# board.net
KiCad netlist of a schematic drawn in EAGLE
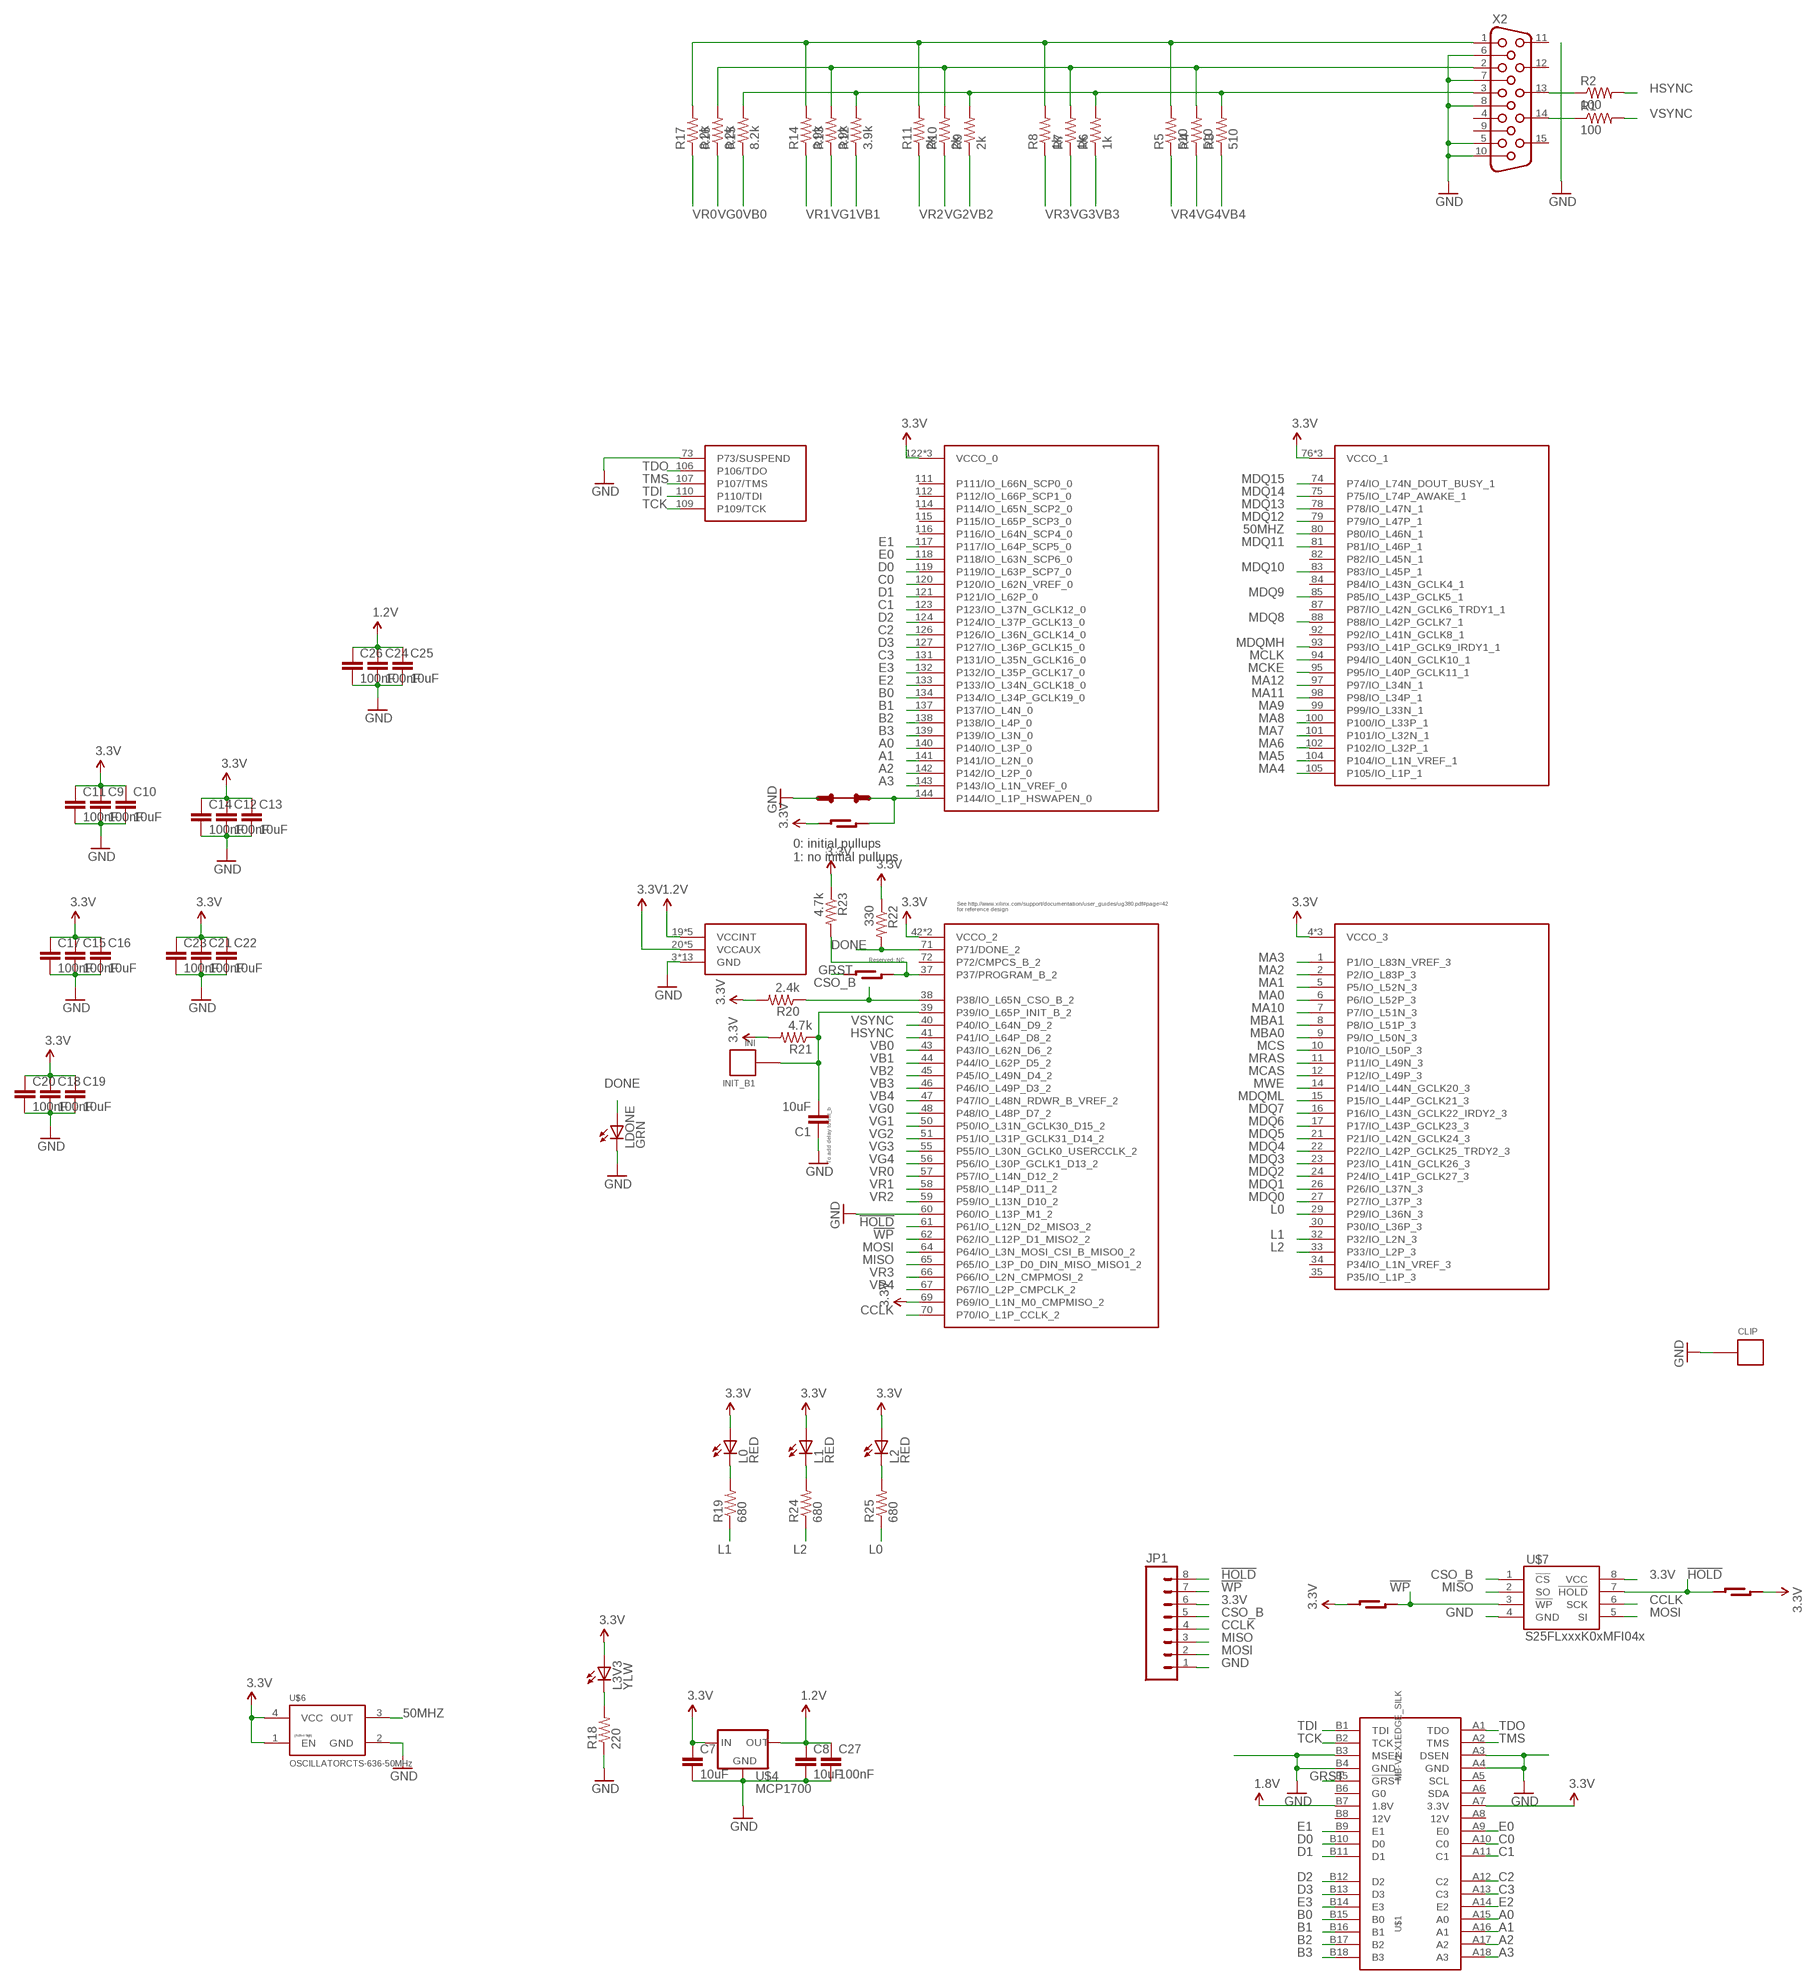
[diagram p0: schematic, sheet 1, part 1 of 2]
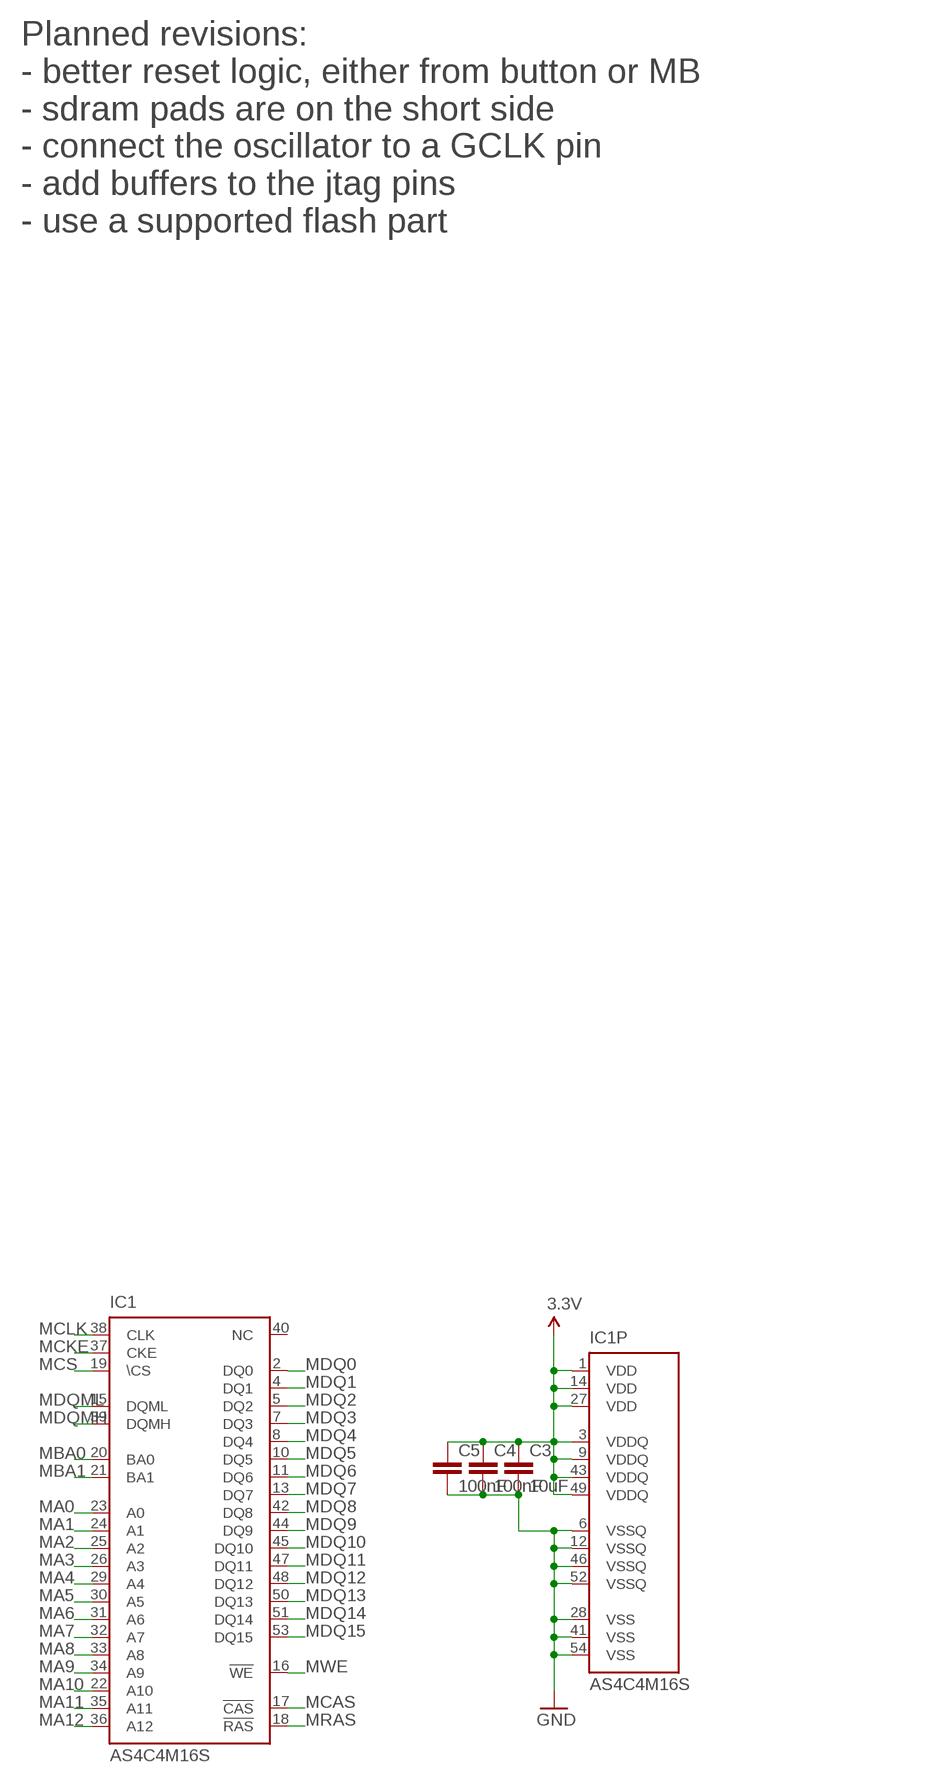
[diagram p1: schematic, sheet 1, part 2 of 2]

(export (version "E")
  (design (tool "Eeschema 10.0.6"))
  (components
    (comp (ref "C1")
      (value "10uF")
      (footprint "eagle-import:0805")
      (libsource (lib "eagle-import") (part "CAP0805"))
    )
    (comp (ref "C3")
      (value "10uF")
      (footprint "eagle-import:0805")
      (libsource (lib "eagle-import") (part "CAP0805"))
    )
    (comp (ref "C4")
      (value "100nF")
      (footprint "eagle-import:0402-CAP")
      (libsource (lib "eagle-import") (part "CAP0402-CAP"))
    )
    (comp (ref "C5")
      (value "100nF")
      (footprint "eagle-import:0402-CAP")
      (libsource (lib "eagle-import") (part "CAP0402-CAP"))
    )
    (comp (ref "C7")
      (value "10uF")
      (footprint "eagle-import:0805")
      (libsource (lib "eagle-import") (part "CAP0805"))
    )
    (comp (ref "C8")
      (value "10uF")
      (footprint "eagle-import:0805")
      (libsource (lib "eagle-import") (part "CAP0805"))
    )
    (comp (ref "C9")
      (value "100nF")
      (footprint "eagle-import:0402-CAP")
      (libsource (lib "eagle-import") (part "CAP0402-CAP"))
    )
    (comp (ref "C10")
      (value "10uF")
      (footprint "eagle-import:0805")
      (libsource (lib "eagle-import") (part "CAP0805"))
    )
    (comp (ref "C11")
      (value "100nF")
      (footprint "eagle-import:0402-CAP")
      (libsource (lib "eagle-import") (part "CAP0402-CAP"))
    )
    (comp (ref "C12")
      (value "100nF")
      (footprint "eagle-import:0402-CAP")
      (libsource (lib "eagle-import") (part "CAP0402-CAP"))
    )
    (comp (ref "C13")
      (value "10uF")
      (footprint "eagle-import:0805")
      (libsource (lib "eagle-import") (part "CAP0805"))
    )
    (comp (ref "C14")
      (value "100nF")
      (footprint "eagle-import:0402-CAP")
      (libsource (lib "eagle-import") (part "CAP0402-CAP"))
    )
    (comp (ref "C15")
      (value "100nF")
      (footprint "eagle-import:0402-CAP")
      (libsource (lib "eagle-import") (part "CAP0402-CAP"))
    )
    (comp (ref "C16")
      (value "10uF")
      (footprint "eagle-import:0805")
      (libsource (lib "eagle-import") (part "CAP0805"))
    )
    (comp (ref "C17")
      (value "100nF")
      (footprint "eagle-import:0402-CAP")
      (libsource (lib "eagle-import") (part "CAP0402-CAP"))
    )
    (comp (ref "C18")
      (value "100nF")
      (footprint "eagle-import:0402-CAP")
      (libsource (lib "eagle-import") (part "CAP0402-CAP"))
    )
    (comp (ref "C19")
      (value "10uF")
      (footprint "eagle-import:0805")
      (libsource (lib "eagle-import") (part "CAP0805"))
    )
    (comp (ref "C20")
      (value "100nF")
      (footprint "eagle-import:0402-CAP")
      (libsource (lib "eagle-import") (part "CAP0402-CAP"))
    )
    (comp (ref "C21")
      (value "100nF")
      (footprint "eagle-import:0402-CAP")
      (libsource (lib "eagle-import") (part "CAP0402-CAP"))
    )
    (comp (ref "C22")
      (value "10uF")
      (footprint "eagle-import:0805")
      (libsource (lib "eagle-import") (part "CAP0805"))
    )
    (comp (ref "C23")
      (value "100nF")
      (footprint "eagle-import:0402-CAP")
      (libsource (lib "eagle-import") (part "CAP0402-CAP"))
    )
    (comp (ref "C24")
      (value "100nF")
      (footprint "eagle-import:0402-CAP")
      (libsource (lib "eagle-import") (part "CAP0402-CAP"))
    )
    (comp (ref "C25")
      (value "10uF")
      (footprint "eagle-import:0805")
      (libsource (lib "eagle-import") (part "CAP0805"))
    )
    (comp (ref "C26")
      (value "100nF")
      (footprint "eagle-import:0402-CAP")
      (libsource (lib "eagle-import") (part "CAP0402-CAP"))
    )
    (comp (ref "C27")
      (value "100nF")
      (footprint "eagle-import:0402-CAP")
      (libsource (lib "eagle-import") (part "CAP0402-CAP"))
    )
    (comp (ref "CLIP")
      (value "CONNECTORCLIP")
      (footprint "eagle-import:CLIP-AREA")
      (libsource (lib "eagle-import") (part "CONNECTORCLIP"))
    )
    (comp (ref "IC1")
      (value "AS4C4M16S")
      (footprint "eagle-import:TSOP54-400")
      (libsource (lib "eagle-import") (part "MT48LC64M4A2"))
    )
    (comp (ref "INIT_B1")
      (value "INI")
      (footprint "eagle-import:TESTPAD-1.27")
      (libsource (lib "eagle-import") (part "CONNECTOR1.27"))
    )
    (comp (ref "JP1")
      (value "M08LOCK")
      (footprint "eagle-import:1X08_LOCK")
      (libsource (lib "eagle-import") (part "M08LOCK"))
    )
    (comp (ref "L0")
      (value "RED")
      (footprint "eagle-import:0603_LED")
      (libsource (lib "eagle-import") (part "LED0603"))
    )
    (comp (ref "L1")
      (value "RED")
      (footprint "eagle-import:0603_LED")
      (libsource (lib "eagle-import") (part "LED0603"))
    )
    (comp (ref "L2")
      (value "RED")
      (footprint "eagle-import:0603_LED")
      (libsource (lib "eagle-import") (part "LED0603"))
    )
    (comp (ref "L3V3")
      (value "YLW")
      (footprint "eagle-import:0603_LED")
      (libsource (lib "eagle-import") (part "LED0603"))
    )
    (comp (ref "LDONE")
      (value "GRN")
      (footprint "eagle-import:0603_LED")
      (libsource (lib "eagle-import") (part "LED0603"))
    )
    (comp (ref "R1")
      (value "100")
      (footprint "eagle-import:0603-RES")
      (libsource (lib "eagle-import") (part "RESISTOR0603"))
    )
    (comp (ref "R2")
      (value "100")
      (footprint "eagle-import:0603-RES")
      (libsource (lib "eagle-import") (part "RESISTOR0603"))
    )
    (comp (ref "R3")
      (value "510")
      (footprint "eagle-import:0603-RES")
      (libsource (lib "eagle-import") (part "RESISTOR0603"))
    )
    (comp (ref "R4")
      (value "510")
      (footprint "eagle-import:0603-RES")
      (libsource (lib "eagle-import") (part "RESISTOR0603"))
    )
    (comp (ref "R5")
      (value "510")
      (footprint "eagle-import:0603-RES")
      (libsource (lib "eagle-import") (part "RESISTOR0603"))
    )
    (comp (ref "R6")
      (value "1k")
      (footprint "eagle-import:0603-RES")
      (libsource (lib "eagle-import") (part "RESISTOR0603"))
    )
    (comp (ref "R7")
      (value "1k")
      (footprint "eagle-import:0603-RES")
      (libsource (lib "eagle-import") (part "RESISTOR0603"))
    )
    (comp (ref "R8")
      (value "1k")
      (footprint "eagle-import:0603-RES")
      (libsource (lib "eagle-import") (part "RESISTOR0603"))
    )
    (comp (ref "R9")
      (value "2k")
      (footprint "eagle-import:0603-RES")
      (libsource (lib "eagle-import") (part "RESISTOR0603"))
    )
    (comp (ref "R10")
      (value "2k")
      (footprint "eagle-import:0603-RES")
      (libsource (lib "eagle-import") (part "RESISTOR0603"))
    )
    (comp (ref "R11")
      (value "2k")
      (footprint "eagle-import:0603-RES")
      (libsource (lib "eagle-import") (part "RESISTOR0603"))
    )
    (comp (ref "R12")
      (value "3.9k")
      (footprint "eagle-import:0603-RES")
      (libsource (lib "eagle-import") (part "RESISTOR0603"))
    )
    (comp (ref "R13")
      (value "3.9k")
      (footprint "eagle-import:0603-RES")
      (libsource (lib "eagle-import") (part "RESISTOR0603"))
    )
    (comp (ref "R14")
      (value "3.9k")
      (footprint "eagle-import:0603-RES")
      (libsource (lib "eagle-import") (part "RESISTOR0603"))
    )
    (comp (ref "R15")
      (value "8.2k")
      (footprint "eagle-import:0603-RES")
      (libsource (lib "eagle-import") (part "RESISTOR0603"))
    )
    (comp (ref "R16")
      (value "8.2k")
      (footprint "eagle-import:0603-RES")
      (libsource (lib "eagle-import") (part "RESISTOR0603"))
    )
    (comp (ref "R17")
      (value "8.2k")
      (footprint "eagle-import:0603-RES")
      (libsource (lib "eagle-import") (part "RESISTOR0603"))
    )
    (comp (ref "R18")
      (value "220")
      (footprint "eagle-import:0603-RES")
      (libsource (lib "eagle-import") (part "RESISTOR0603"))
    )
    (comp (ref "R19")
      (value "680")
      (footprint "eagle-import:0603-RES")
      (libsource (lib "eagle-import") (part "RESISTOR0603"))
    )
    (comp (ref "R20")
      (value "2.4k")
      (footprint "eagle-import:0603-RES")
      (libsource (lib "eagle-import") (part "RESISTOR0603"))
    )
    (comp (ref "R21")
      (value "4.7k")
      (footprint "eagle-import:0603-RES")
      (libsource (lib "eagle-import") (part "RESISTOR0603"))
    )
    (comp (ref "R22")
      (value "330")
      (footprint "eagle-import:0603-RES")
      (libsource (lib "eagle-import") (part "RESISTOR0603"))
    )
    (comp (ref "R23")
      (value "4.7k")
      (footprint "eagle-import:0603-RES")
      (libsource (lib "eagle-import") (part "RESISTOR0603"))
    )
    (comp (ref "R24")
      (value "680")
      (footprint "eagle-import:0603-RES")
      (libsource (lib "eagle-import") (part "RESISTOR0603"))
    )
    (comp (ref "R25")
      (value "680")
      (footprint "eagle-import:0603-RES")
      (libsource (lib "eagle-import") (part "RESISTOR0603"))
    )
    (comp (ref "SB1")
      (value "SOLDER-BRIDGEOPEN")
      (footprint "eagle-import:SOLDER-BRIDGE-OPEN")
      (libsource (lib "eagle-import") (part "SOLDER-BRIDGEOPEN"))
    )
    (comp (ref "SB2")
      (value "TRACE-CUT")
      (footprint "eagle-import:TRACE-CUT")
      (libsource (lib "eagle-import") (part "TRACE-CUT"))
    )
    (comp (ref "SB3")
      (value "SOLDER-BRIDGEOPEN")
      (footprint "eagle-import:SOLDER-BRIDGE-OPEN")
      (libsource (lib "eagle-import") (part "SOLDER-BRIDGEOPEN"))
    )
    (comp (ref "SB4")
      (value "SOLDER-BRIDGEOPEN")
      (footprint "eagle-import:SOLDER-BRIDGE-OPEN")
      (libsource (lib "eagle-import") (part "SOLDER-BRIDGEOPEN"))
    )
    (comp (ref "SB5")
      (value "SOLDER-BRIDGEOPEN")
      (footprint "eagle-import:SOLDER-BRIDGE-OPEN")
      (libsource (lib "eagle-import") (part "SOLDER-BRIDGEOPEN"))
    )
    (comp (ref "U$1")
      (value "MB-V1-X1EDGE_SILK")
      (footprint "eagle-import:MB-V1-X1-EDGE")
      (libsource (lib "eagle-import") (part "MB-V1-X1EDGE_SILK"))
    )
    (comp (ref "U$4")
      (value "MCP1700")
      (footprint "eagle-import:SOT23-3")
      (libsource (lib "eagle-import") (part "VREGSOT23-3"))
    )
    (comp (ref "U$6")
      (value "OSCILLATORCTS-636-50MHz")
      (footprint "eagle-import:CTS-636")
      (libsource (lib "eagle-import") (part "OSCILLATORCTS-636"))
    )
    (comp (ref "U$7")
      (value "S25FLxxxK0xMFI04x")
      (footprint "eagle-import:SO08")
      (libsource (lib "eagle-import") (part "S25FL"))
    )
    (comp (ref "U$9")
      (value "XC6SLX-TQ144")
      (footprint "eagle-import:XILINX_TQ144")
      (libsource (lib "eagle-import") (part "XC6SLX-TQ144"))
    )
    (comp (ref "X2")
      (value "HF15H")
      (footprint "eagle-import:HDF15H")
      (libsource (lib "eagle-import") (part "HF15H"))
    )
  )
  (nets
    (net (code "1") (name "/50MHZ") (class "Default")
      (node (ref "U$6") (pin "3") (pinfunction "OUT_3") (pintype "bidirectional"))
      (node (ref "U$9") (pin "80") (pinfunction "P80/IO_L46N_1_80") (pintype "bidirectional"))
    )
    (net (code "2") (name "/A0") (class "Default")
      (node (ref "U$1") (pin "A15") (pinfunction "A0_A15") (pintype "bidirectional"))
      (node (ref "U$9") (pin "140") (pinfunction "P140/IO_L3P_0_140") (pintype "bidirectional"))
    )
    (net (code "3") (name "/A1") (class "Default")
      (node (ref "U$1") (pin "A16") (pinfunction "A1_A16") (pintype "bidirectional"))
      (node (ref "U$9") (pin "141") (pinfunction "P141/IO_L2N_0_141") (pintype "bidirectional"))
    )
    (net (code "4") (name "/A2") (class "Default")
      (node (ref "U$1") (pin "A17") (pinfunction "A2_A17") (pintype "bidirectional"))
      (node (ref "U$9") (pin "142") (pinfunction "P142/IO_L2P_0_142") (pintype "bidirectional"))
    )
    (net (code "5") (name "/A3") (class "Default")
      (node (ref "U$1") (pin "A18") (pinfunction "A3_A18") (pintype "bidirectional"))
      (node (ref "U$9") (pin "143") (pinfunction "P143/IO_L1N_VREF_0_143") (pintype "bidirectional"))
    )
    (net (code "6") (name "/B0") (class "Default")
      (node (ref "U$1") (pin "B15") (pinfunction "B0_B15") (pintype "bidirectional"))
      (node (ref "U$9") (pin "134") (pinfunction "P134/IO_L34P_GCLK19_0_134") (pintype "bidirectional"))
    )
    (net (code "7") (name "/B1") (class "Default")
      (node (ref "U$1") (pin "B16") (pinfunction "B1_B16") (pintype "bidirectional"))
      (node (ref "U$9") (pin "137") (pinfunction "P137/IO_L4N_0_137") (pintype "bidirectional"))
    )
    (net (code "8") (name "/B2") (class "Default")
      (node (ref "U$1") (pin "B17") (pinfunction "B2_B17") (pintype "bidirectional"))
      (node (ref "U$9") (pin "138") (pinfunction "P138/IO_L4P_0_138") (pintype "bidirectional"))
    )
    (net (code "9") (name "/B3") (class "Default")
      (node (ref "U$1") (pin "B18") (pinfunction "B3_B18") (pintype "bidirectional"))
      (node (ref "U$9") (pin "139") (pinfunction "P139/IO_L3N_0_139") (pintype "bidirectional"))
    )
    (net (code "10") (name "/C0") (class "Default")
      (node (ref "U$1") (pin "A10") (pinfunction "C0_A10") (pintype "bidirectional"))
      (node (ref "U$9") (pin "120") (pinfunction "P120/IO_L62N_VREF_0_120") (pintype "bidirectional"))
    )
    (net (code "11") (name "/C1") (class "Default")
      (node (ref "U$1") (pin "A11") (pinfunction "C1_A11") (pintype "bidirectional"))
      (node (ref "U$9") (pin "123") (pinfunction "P123/IO_L37N_GCLK12_0_123") (pintype "bidirectional"))
    )
    (net (code "12") (name "/C2") (class "Default")
      (node (ref "U$1") (pin "A12") (pinfunction "C2_A12") (pintype "bidirectional"))
      (node (ref "U$9") (pin "126") (pinfunction "P126/IO_L36N_GCLK14_0_126") (pintype "bidirectional"))
    )
    (net (code "13") (name "/C3") (class "Default")
      (node (ref "U$1") (pin "A13") (pinfunction "C3_A13") (pintype "bidirectional"))
      (node (ref "U$9") (pin "131") (pinfunction "P131/IO_L35N_GCLK16_0_131") (pintype "bidirectional"))
    )
    (net (code "14") (name "/CCLK") (class "Default")
      (node (ref "JP1") (pin "4") (pinfunction "4_4") (pintype "passive"))
      (node (ref "U$7") (pin "6") (pinfunction "SCK_6") (pintype "bidirectional"))
      (node (ref "U$9") (pin "70") (pinfunction "P70/IO_L1P_CCLK_2_70") (pintype "bidirectional"))
    )
    (net (code "15") (name "/CSO_B") (class "Default")
      (node (ref "JP1") (pin "5") (pinfunction "5_5") (pintype "passive"))
      (node (ref "R20") (pin "1") (pinfunction "1_1") (pintype "passive"))
      (node (ref "U$7") (pin "1") (pinfunction "~{CS}_1") (pintype "bidirectional"))
      (node (ref "U$9") (pin "38") (pinfunction "P38/IO_L65N_CSO_B_2_38") (pintype "bidirectional"))
    )
    (net (code "16") (name "/D0") (class "Default")
      (node (ref "U$1") (pin "B10") (pinfunction "D0_B10") (pintype "bidirectional"))
      (node (ref "U$9") (pin "119") (pinfunction "P119/IO_L63P_SCP7_0_119") (pintype "bidirectional"))
    )
    (net (code "17") (name "/D1") (class "Default")
      (node (ref "U$1") (pin "B11") (pinfunction "D1_B11") (pintype "bidirectional"))
      (node (ref "U$9") (pin "121") (pinfunction "P121/IO_L62P_0_121") (pintype "bidirectional"))
    )
    (net (code "18") (name "/D2") (class "Default")
      (node (ref "U$1") (pin "B12") (pinfunction "D2_B12") (pintype "bidirectional"))
      (node (ref "U$9") (pin "124") (pinfunction "P124/IO_L37P_GCLK13_0_124") (pintype "bidirectional"))
    )
    (net (code "19") (name "/D3") (class "Default")
      (node (ref "U$1") (pin "B13") (pinfunction "D3_B13") (pintype "bidirectional"))
      (node (ref "U$9") (pin "127") (pinfunction "P127/IO_L36P_GCLK15_0_127") (pintype "bidirectional"))
    )
    (net (code "20") (name "/DONE") (class "Default")
      (node (ref "LDONE") (pin "A") (pinfunction "A_A") (pintype "passive"))
      (node (ref "R22") (pin "2") (pinfunction "2_2") (pintype "passive"))
      (node (ref "U$9") (pin "71") (pinfunction "P71/DONE_2_71") (pintype "bidirectional"))
    )
    (net (code "21") (name "/E0") (class "Default")
      (node (ref "U$1") (pin "A9") (pinfunction "E0_A9") (pintype "bidirectional"))
      (node (ref "U$9") (pin "118") (pinfunction "P118/IO_L63N_SCP6_0_118") (pintype "bidirectional"))
    )
    (net (code "22") (name "/E1") (class "Default")
      (node (ref "U$1") (pin "B9") (pinfunction "E1_B9") (pintype "bidirectional"))
      (node (ref "U$9") (pin "117") (pinfunction "P117/IO_L64P_SCP5_0_117") (pintype "bidirectional"))
    )
    (net (code "23") (name "/E2") (class "Default")
      (node (ref "U$1") (pin "A14") (pinfunction "E2_A14") (pintype "bidirectional"))
      (node (ref "U$9") (pin "133") (pinfunction "P133/IO_L34N_GCLK18_0_133") (pintype "bidirectional"))
    )
    (net (code "24") (name "/E3") (class "Default")
      (node (ref "U$1") (pin "B14") (pinfunction "E3_B14") (pintype "bidirectional"))
      (node (ref "U$9") (pin "132") (pinfunction "P132/IO_L35P_GCLK17_0_132") (pintype "bidirectional"))
    )
    (net (code "25") (name "/GRST") (class "Default")
      (node (ref "SB5") (pin "L1") (pinfunction "P$1_L1") (pintype "passive"))
      (node (ref "SB5") (pin "L2") (pinfunction "P$1_L2") (pintype "passive"))
      (node (ref "U$1") (pin "B5") (pinfunction "~{GRST}_B5") (pintype "bidirectional"))
    )
    (net (code "26") (name "/HSYNC") (class "Default")
      (node (ref "R2") (pin "2") (pinfunction "2_2") (pintype "passive"))
      (node (ref "U$9") (pin "41") (pinfunction "P41/IO_L64P_D8_2_41") (pintype "bidirectional"))
    )
    (net (code "27") (name "/L0") (class "Default")
      (node (ref "R25") (pin "1") (pinfunction "1_1") (pintype "passive"))
      (node (ref "U$9") (pin "29") (pinfunction "P29/IO_L36N_3_29") (pintype "bidirectional"))
    )
    (net (code "28") (name "/L1") (class "Default")
      (node (ref "R19") (pin "1") (pinfunction "1_1") (pintype "passive"))
      (node (ref "U$9") (pin "32") (pinfunction "P32/IO_L2N_3_32") (pintype "bidirectional"))
    )
    (net (code "29") (name "/L2") (class "Default")
      (node (ref "R24") (pin "1") (pinfunction "1_1") (pintype "passive"))
      (node (ref "U$9") (pin "33") (pinfunction "P33/IO_L2P_3_33") (pintype "bidirectional"))
    )
    (net (code "30") (name "/MA0") (class "Default")
      (node (ref "IC1") (pin "23") (pinfunction "A0_23") (pintype "input"))
      (node (ref "U$9") (pin "6") (pinfunction "P6/IO_L52P_3_6") (pintype "bidirectional"))
    )
    (net (code "31") (name "/MA1") (class "Default")
      (node (ref "IC1") (pin "24") (pinfunction "A1_24") (pintype "input"))
      (node (ref "U$9") (pin "5") (pinfunction "P5/IO_L52N_3_5") (pintype "bidirectional"))
    )
    (net (code "32") (name "/MA2") (class "Default")
      (node (ref "IC1") (pin "25") (pinfunction "A2_25") (pintype "input"))
      (node (ref "U$9") (pin "2") (pinfunction "P2/IO_L83P_3_2") (pintype "bidirectional"))
    )
    (net (code "33") (name "/MA3") (class "Default")
      (node (ref "IC1") (pin "26") (pinfunction "A3_26") (pintype "input"))
      (node (ref "U$9") (pin "1") (pinfunction "P1/IO_L83N_VREF_3_1") (pintype "bidirectional"))
    )
    (net (code "34") (name "/MA4") (class "Default")
      (node (ref "IC1") (pin "29") (pinfunction "A4_29") (pintype "input"))
      (node (ref "U$9") (pin "105") (pinfunction "P105/IO_L1P_1_105") (pintype "bidirectional"))
    )
    (net (code "35") (name "/MA5") (class "Default")
      (node (ref "IC1") (pin "30") (pinfunction "A5_30") (pintype "input"))
      (node (ref "U$9") (pin "104") (pinfunction "P104/IO_L1N_VREF_1_104") (pintype "bidirectional"))
    )
    (net (code "36") (name "/MA6") (class "Default")
      (node (ref "IC1") (pin "31") (pinfunction "A6_31") (pintype "input"))
      (node (ref "U$9") (pin "102") (pinfunction "P102/IO_L32P_1_102") (pintype "bidirectional"))
    )
    (net (code "37") (name "/MA7") (class "Default")
      (node (ref "IC1") (pin "32") (pinfunction "A7_32") (pintype "input"))
      (node (ref "U$9") (pin "101") (pinfunction "P101/IO_L32N_1_101") (pintype "bidirectional"))
    )
    (net (code "38") (name "/MA8") (class "Default")
      (node (ref "IC1") (pin "33") (pinfunction "A8_33") (pintype "input"))
      (node (ref "U$9") (pin "100") (pinfunction "P100/IO_L33P_1_100") (pintype "bidirectional"))
    )
    (net (code "39") (name "/MA9") (class "Default")
      (node (ref "IC1") (pin "34") (pinfunction "A9_34") (pintype "input"))
      (node (ref "U$9") (pin "99") (pinfunction "P99/IO_L33N_1_99") (pintype "bidirectional"))
    )
    (net (code "40") (name "/MA10") (class "Default")
      (node (ref "IC1") (pin "22") (pinfunction "A10_22") (pintype "input"))
      (node (ref "U$9") (pin "7") (pinfunction "P7/IO_L51N_3_7") (pintype "bidirectional"))
    )
    (net (code "41") (name "/MA11") (class "Default")
      (node (ref "IC1") (pin "35") (pinfunction "A11_35") (pintype "input"))
      (node (ref "U$9") (pin "98") (pinfunction "P98/IO_L34P_1_98") (pintype "bidirectional"))
    )
    (net (code "42") (name "/MA12") (class "Default")
      (node (ref "IC1") (pin "36") (pinfunction "A12_36") (pintype "input"))
      (node (ref "U$9") (pin "97") (pinfunction "P97/IO_L34N_1_97") (pintype "bidirectional"))
    )
    (net (code "43") (name "/MBA0") (class "Default")
      (node (ref "IC1") (pin "20") (pinfunction "BA0_20") (pintype "input"))
      (node (ref "U$9") (pin "9") (pinfunction "P9/IO_L50N_3_9") (pintype "bidirectional"))
    )
    (net (code "44") (name "/MBA1") (class "Default")
      (node (ref "IC1") (pin "21") (pinfunction "BA1_21") (pintype "input"))
      (node (ref "U$9") (pin "8") (pinfunction "P8/IO_L51P_3_8") (pintype "bidirectional"))
    )
    (net (code "45") (name "/MCAS") (class "Default")
      (node (ref "IC1") (pin "17") (pinfunction "~{CAS}_17") (pintype "input"))
      (node (ref "U$9") (pin "12") (pinfunction "P12/IO_L49P_3_12") (pintype "bidirectional"))
    )
    (net (code "46") (name "/MCKE") (class "Default")
      (node (ref "IC1") (pin "37") (pinfunction "CKE_37") (pintype "input"))
      (node (ref "U$9") (pin "95") (pinfunction "P95/IO_L40P_GCLK11_1_95") (pintype "bidirectional"))
    )
    (net (code "47") (name "/MCLK") (class "Default")
      (node (ref "IC1") (pin "38") (pinfunction "CLK_38") (pintype "input"))
      (node (ref "U$9") (pin "94") (pinfunction "P94/IO_L40N_GCLK10_1_94") (pintype "bidirectional"))
    )
    (net (code "48") (name "/MCS") (class "Default")
      (node (ref "IC1") (pin "19") (pinfunction "\\CS_19") (pintype "input"))
      (node (ref "U$9") (pin "10") (pinfunction "P10/IO_L50P_3_10") (pintype "bidirectional"))
    )
    (net (code "49") (name "/MDQ0") (class "Default")
      (node (ref "IC1") (pin "2") (pinfunction "DQ0_2") (pintype "tri_state"))
      (node (ref "U$9") (pin "27") (pinfunction "P27/IO_L37P_3_27") (pintype "bidirectional"))
    )
    (net (code "50") (name "/MDQ1") (class "Default")
      (node (ref "IC1") (pin "4") (pinfunction "DQ1_4") (pintype "tri_state"))
      (node (ref "U$9") (pin "26") (pinfunction "P26/IO_L37N_3_26") (pintype "bidirectional"))
    )
    (net (code "51") (name "/MDQ2") (class "Default")
      (node (ref "IC1") (pin "5") (pinfunction "DQ2_5") (pintype "tri_state"))
      (node (ref "U$9") (pin "24") (pinfunction "P24/IO_L41P_GCLK27_3_24") (pintype "bidirectional"))
    )
    (net (code "52") (name "/MDQ3") (class "Default")
      (node (ref "IC1") (pin "7") (pinfunction "DQ3_7") (pintype "tri_state"))
      (node (ref "U$9") (pin "23") (pinfunction "P23/IO_L41N_GCLK26_3_23") (pintype "bidirectional"))
    )
    (net (code "53") (name "/MDQ4") (class "Default")
      (node (ref "IC1") (pin "8") (pinfunction "DQ4_8") (pintype "tri_state"))
      (node (ref "U$9") (pin "22") (pinfunction "P22/IO_L42P_GCLK25_TRDY2_3_22") (pintype "bidirectional"))
    )
    (net (code "54") (name "/MDQ5") (class "Default")
      (node (ref "IC1") (pin "10") (pinfunction "DQ5_10") (pintype "tri_state"))
      (node (ref "U$9") (pin "21") (pinfunction "P21/IO_L42N_GCLK24_3_21") (pintype "bidirectional"))
    )
    (net (code "55") (name "/MDQ6") (class "Default")
      (node (ref "IC1") (pin "11") (pinfunction "DQ6_11") (pintype "tri_state"))
      (node (ref "U$9") (pin "17") (pinfunction "P17/IO_L43P_GCLK23_3_17") (pintype "bidirectional"))
    )
    (net (code "56") (name "/MDQ7") (class "Default")
      (node (ref "IC1") (pin "13") (pinfunction "DQ7_13") (pintype "tri_state"))
      (node (ref "U$9") (pin "16") (pinfunction "P16/IO_L43N_GCLK22_IRDY2_3_16") (pintype "bidirectional"))
    )
    (net (code "57") (name "/MDQ8") (class "Default")
      (node (ref "IC1") (pin "42") (pinfunction "DQ8_42") (pintype "tri_state"))
      (node (ref "U$9") (pin "88") (pinfunction "P88/IO_L42P_GCLK7_1_88") (pintype "bidirectional"))
    )
    (net (code "58") (name "/MDQ9") (class "Default")
      (node (ref "IC1") (pin "44") (pinfunction "DQ9_44") (pintype "tri_state"))
      (node (ref "U$9") (pin "85") (pinfunction "P85/IO_L43P_GCLK5_1_85") (pintype "bidirectional"))
    )
    (net (code "59") (name "/MDQ10") (class "Default")
      (node (ref "IC1") (pin "45") (pinfunction "DQ10_45") (pintype "tri_state"))
      (node (ref "U$9") (pin "83") (pinfunction "P83/IO_L45P_1_83") (pintype "bidirectional"))
    )
    (net (code "60") (name "/MDQ11") (class "Default")
      (node (ref "IC1") (pin "47") (pinfunction "DQ11_47") (pintype "tri_state"))
      (node (ref "U$9") (pin "81") (pinfunction "P81/IO_L46P_1_81") (pintype "bidirectional"))
    )
    (net (code "61") (name "/MDQ12") (class "Default")
      (node (ref "IC1") (pin "48") (pinfunction "DQ12_48") (pintype "tri_state"))
      (node (ref "U$9") (pin "79") (pinfunction "P79/IO_L47P_1_79") (pintype "bidirectional"))
    )
    (net (code "62") (name "/MDQ13") (class "Default")
      (node (ref "IC1") (pin "50") (pinfunction "DQ13_50") (pintype "tri_state"))
      (node (ref "U$9") (pin "78") (pinfunction "P78/IO_L47N_1_78") (pintype "bidirectional"))
    )
    (net (code "63") (name "/MDQ14") (class "Default")
      (node (ref "IC1") (pin "51") (pinfunction "DQ14_51") (pintype "tri_state"))
      (node (ref "U$9") (pin "75") (pinfunction "P75/IO_L74P_AWAKE_1_75") (pintype "bidirectional"))
    )
    (net (code "64") (name "/MDQ15") (class "Default")
      (node (ref "IC1") (pin "53") (pinfunction "DQ15_53") (pintype "tri_state"))
      (node (ref "U$9") (pin "74") (pinfunction "P74/IO_L74N_DOUT_BUSY_1_74") (pintype "bidirectional"))
    )
    (net (code "65") (name "/MDQMH") (class "Default")
      (node (ref "IC1") (pin "39") (pinfunction "DQMH_39") (pintype "input"))
      (node (ref "U$9") (pin "93") (pinfunction "P93/IO_L41P_GCLK9_IRDY1_1_93") (pintype "bidirectional"))
    )
    (net (code "66") (name "/MDQML") (class "Default")
      (node (ref "IC1") (pin "15") (pinfunction "DQML_15") (pintype "input"))
      (node (ref "U$9") (pin "15") (pinfunction "P15/IO_L44P_GCLK21_3_15") (pintype "bidirectional"))
    )
    (net (code "67") (name "/MISO") (class "Default")
      (node (ref "JP1") (pin "3") (pinfunction "3_3") (pintype "passive"))
      (node (ref "U$7") (pin "2") (pinfunction "SO_2") (pintype "bidirectional"))
      (node (ref "U$9") (pin "65") (pinfunction "P65/IO_L3P_D0_DIN_MISO_MISO1_2_65") (pintype "bidirectional"))
    )
    (net (code "68") (name "/MOSI") (class "Default")
      (node (ref "JP1") (pin "2") (pinfunction "2_2") (pintype "passive"))
      (node (ref "U$7") (pin "5") (pinfunction "SI_5") (pintype "bidirectional"))
      (node (ref "U$9") (pin "64") (pinfunction "P64/IO_L3N_MOSI_CSI_B_MISO0_2_64") (pintype "bidirectional"))
    )
    (net (code "69") (name "/MRAS") (class "Default")
      (node (ref "IC1") (pin "18") (pinfunction "~{RAS}_18") (pintype "input"))
      (node (ref "U$9") (pin "11") (pinfunction "P11/IO_L49N_3_11") (pintype "bidirectional"))
    )
    (net (code "70") (name "/MWE") (class "Default")
      (node (ref "IC1") (pin "16") (pinfunction "~{WE}_16") (pintype "input"))
      (node (ref "U$9") (pin "14") (pinfunction "P14/IO_L44N_GCLK20_3_14") (pintype "bidirectional"))
    )
    (net (code "71") (name "/TCK") (class "Default")
      (node (ref "U$1") (pin "B2") (pinfunction "TCK_B2") (pintype "bidirectional"))
      (node (ref "U$9") (pin "109") (pinfunction "P109/TCK_109") (pintype "bidirectional"))
    )
    (net (code "72") (name "/TDI") (class "Default")
      (node (ref "U$1") (pin "B1") (pinfunction "TDI_B1") (pintype "bidirectional"))
      (node (ref "U$9") (pin "110") (pinfunction "P110/TDI_110") (pintype "bidirectional"))
    )
    (net (code "73") (name "/TDO") (class "Default")
      (node (ref "U$1") (pin "A1") (pinfunction "TDO_A1") (pintype "bidirectional"))
      (node (ref "U$9") (pin "106") (pinfunction "P106/TDO_106") (pintype "bidirectional"))
    )
    (net (code "74") (name "/TMS") (class "Default")
      (node (ref "U$1") (pin "A2") (pinfunction "TMS_A2") (pintype "bidirectional"))
      (node (ref "U$9") (pin "107") (pinfunction "P107/TMS_107") (pintype "bidirectional"))
    )
    (net (code "75") (name "/VB0") (class "Default")
      (node (ref "R15") (pin "1") (pinfunction "1_1") (pintype "passive"))
      (node (ref "U$9") (pin "43") (pinfunction "P43/IO_L62N_D6_2_43") (pintype "bidirectional"))
    )
    (net (code "76") (name "/VB1") (class "Default")
      (node (ref "R12") (pin "1") (pinfunction "1_1") (pintype "passive"))
      (node (ref "U$9") (pin "44") (pinfunction "P44/IO_L62P_D5_2_44") (pintype "bidirectional"))
    )
    (net (code "77") (name "/VB2") (class "Default")
      (node (ref "R9") (pin "1") (pinfunction "1_1") (pintype "passive"))
      (node (ref "U$9") (pin "45") (pinfunction "P45/IO_L49N_D4_2_45") (pintype "bidirectional"))
    )
    (net (code "78") (name "/VB3") (class "Default")
      (node (ref "R6") (pin "1") (pinfunction "1_1") (pintype "passive"))
      (node (ref "U$9") (pin "46") (pinfunction "P46/IO_L49P_D3_2_46") (pintype "bidirectional"))
    )
    (net (code "79") (name "/VB4") (class "Default")
      (node (ref "R3") (pin "1") (pinfunction "1_1") (pintype "passive"))
      (node (ref "U$9") (pin "47") (pinfunction "P47/IO_L48N_RDWR_B_VREF_2_47") (pintype "bidirectional"))
    )
    (net (code "80") (name "/VG0") (class "Default")
      (node (ref "R16") (pin "1") (pinfunction "1_1") (pintype "passive"))
      (node (ref "U$9") (pin "48") (pinfunction "P48/IO_L48P_D7_2_48") (pintype "bidirectional"))
    )
    (net (code "81") (name "/VG1") (class "Default")
      (node (ref "R13") (pin "1") (pinfunction "1_1") (pintype "passive"))
      (node (ref "U$9") (pin "50") (pinfunction "P50/IO_L31N_GCLK30_D15_2_50") (pintype "bidirectional"))
    )
    (net (code "82") (name "/VG2") (class "Default")
      (node (ref "R10") (pin "1") (pinfunction "1_1") (pintype "passive"))
      (node (ref "U$9") (pin "51") (pinfunction "P51/IO_L31P_GCLK31_D14_2_51") (pintype "bidirectional"))
    )
    (net (code "83") (name "/VG3") (class "Default")
      (node (ref "R7") (pin "1") (pinfunction "1_1") (pintype "passive"))
      (node (ref "U$9") (pin "55") (pinfunction "P55/IO_L30N_GCLK0_USERCCLK_2_55") (pintype "bidirectional"))
    )
    (net (code "84") (name "/VG4") (class "Default")
      (node (ref "R4") (pin "1") (pinfunction "1_1") (pintype "passive"))
      (node (ref "U$9") (pin "56") (pinfunction "P56/IO_L30P_GCLK1_D13_2_56") (pintype "bidirectional"))
    )
    (net (code "85") (name "/VR0") (class "Default")
      (node (ref "R17") (pin "1") (pinfunction "1_1") (pintype "passive"))
      (node (ref "U$9") (pin "57") (pinfunction "P57/IO_L14N_D12_2_57") (pintype "bidirectional"))
    )
    (net (code "86") (name "/VR1") (class "Default")
      (node (ref "R14") (pin "1") (pinfunction "1_1") (pintype "passive"))
      (node (ref "U$9") (pin "58") (pinfunction "P58/IO_L14P_D11_2_58") (pintype "bidirectional"))
    )
    (net (code "87") (name "/VR2") (class "Default")
      (node (ref "R11") (pin "1") (pinfunction "1_1") (pintype "passive"))
      (node (ref "U$9") (pin "59") (pinfunction "P59/IO_L13N_D10_2_59") (pintype "bidirectional"))
    )
    (net (code "88") (name "/VR3") (class "Default")
      (node (ref "R8") (pin "1") (pinfunction "1_1") (pintype "passive"))
      (node (ref "U$9") (pin "66") (pinfunction "P66/IO_L2N_CMPMOSI_2_66") (pintype "bidirectional"))
    )
    (net (code "89") (name "/VR4") (class "Default")
      (node (ref "R5") (pin "1") (pinfunction "1_1") (pintype "passive"))
      (node (ref "U$9") (pin "67") (pinfunction "P67/IO_L2P_CMPCLK_2_67") (pintype "bidirectional"))
    )
    (net (code "90") (name "/VSYNC") (class "Default")
      (node (ref "R1") (pin "2") (pinfunction "2_2") (pintype "passive"))
      (node (ref "U$9") (pin "40") (pinfunction "P40/IO_L64N_D9_2_40") (pintype "bidirectional"))
    )
    (net (code "91") (name "/~{HOLD}") (class "Default")
      (node (ref "JP1") (pin "8") (pinfunction "8_8") (pintype "passive"))
      (node (ref "SB3") (pin "R1") (pinfunction "P$2_R1") (pintype "passive"))
      (node (ref "SB3") (pin "R2") (pinfunction "P$2_R2") (pintype "passive"))
      (node (ref "U$7") (pin "7") (pinfunction "~{HOLD}_7") (pintype "bidirectional"))
      (node (ref "U$9") (pin "61") (pinfunction "P61/IO_L12N_D2_MISO3_2_61") (pintype "bidirectional"))
    )
    (net (code "92") (name "/~{WP}") (class "Default")
      (node (ref "JP1") (pin "7") (pinfunction "7_7") (pintype "passive"))
      (node (ref "SB4") (pin "L1") (pinfunction "P$1_L1") (pintype "passive"))
      (node (ref "SB4") (pin "L2") (pinfunction "P$1_L2") (pintype "passive"))
      (node (ref "U$7") (pin "3") (pinfunction "~{WP}_3") (pintype "bidirectional"))
      (node (ref "U$9") (pin "62") (pinfunction "P62/IO_L12P_D1_MISO2_2_62") (pintype "bidirectional"))
    )
    (net (code "93") (name "1.2V") (class "Default")
      (node (ref "C24") (pin "1") (pinfunction "1_1") (pintype "passive"))
      (node (ref "C25") (pin "1") (pinfunction "1_1") (pintype "passive"))
      (node (ref "C26") (pin "1") (pinfunction "1_1") (pintype "passive"))
      (node (ref "C27") (pin "1") (pinfunction "1_1") (pintype "passive"))
      (node (ref "C8") (pin "1") (pinfunction "1_1") (pintype "passive"))
      (node (ref "U$4") (pin "2") (pinfunction "OUT_2") (pintype "passive"))
      (node (ref "U$9") (pin "128") (pinfunction "VCCINT_128") (pintype "bidirectional"))
      (node (ref "U$9") (pin "19") (pinfunction "VCCINT_19") (pintype "bidirectional"))
      (node (ref "U$9") (pin "28") (pinfunction "VCCINT_28") (pintype "bidirectional"))
      (node (ref "U$9") (pin "52") (pinfunction "VCCINT_52") (pintype "bidirectional"))
      (node (ref "U$9") (pin "89") (pinfunction "VCCINT_89") (pintype "bidirectional"))
    )
    (net (code "94") (name "1.8V") (class "Default")
      (node (ref "U$1") (pin "B7") (pinfunction "1.8V_B7") (pintype "bidirectional"))
    )
    (net (code "95") (name "3.3V") (class "Default")
      (node (ref "C10") (pin "1") (pinfunction "1_1") (pintype "passive"))
      (node (ref "C11") (pin "1") (pinfunction "1_1") (pintype "passive"))
      (node (ref "C12") (pin "1") (pinfunction "1_1") (pintype "passive"))
      (node (ref "C13") (pin "1") (pinfunction "1_1") (pintype "passive"))
      (node (ref "C14") (pin "1") (pinfunction "1_1") (pintype "passive"))
      (node (ref "C15") (pin "1") (pinfunction "1_1") (pintype "passive"))
      (node (ref "C16") (pin "1") (pinfunction "1_1") (pintype "passive"))
      (node (ref "C17") (pin "1") (pinfunction "1_1") (pintype "passive"))
      (node (ref "C18") (pin "1") (pinfunction "1_1") (pintype "passive"))
      (node (ref "C19") (pin "1") (pinfunction "1_1") (pintype "passive"))
      (node (ref "C20") (pin "1") (pinfunction "1_1") (pintype "passive"))
      (node (ref "C21") (pin "1") (pinfunction "1_1") (pintype "passive"))
      (node (ref "C22") (pin "1") (pinfunction "1_1") (pintype "passive"))
      (node (ref "C23") (pin "1") (pinfunction "1_1") (pintype "passive"))
      (node (ref "C3") (pin "1") (pinfunction "1_1") (pintype "passive"))
      (node (ref "C4") (pin "1") (pinfunction "1_1") (pintype "passive"))
      (node (ref "C5") (pin "1") (pinfunction "1_1") (pintype "passive"))
      (node (ref "C7") (pin "1") (pinfunction "1_1") (pintype "passive"))
      (node (ref "C9") (pin "1") (pinfunction "1_1") (pintype "passive"))
      (node (ref "IC1") (pin "1") (pinfunction "VDD_1") (pintype "input"))
      (node (ref "IC1") (pin "14") (pinfunction "VDD_14") (pintype "input"))
      (node (ref "IC1") (pin "27") (pinfunction "VDD_27") (pintype "input"))
      (node (ref "IC1") (pin "3") (pinfunction "VDDQ_3") (pintype "input"))
      (node (ref "IC1") (pin "43") (pinfunction "VDDQ_43") (pintype "input"))
      (node (ref "IC1") (pin "49") (pinfunction "VDDQ_49") (pintype "input"))
      (node (ref "IC1") (pin "9") (pinfunction "VDDQ_9") (pintype "input"))
      (node (ref "JP1") (pin "6") (pinfunction "6_6") (pintype "passive"))
      (node (ref "L0") (pin "A") (pinfunction "A_A") (pintype "passive"))
      (node (ref "L1") (pin "A") (pinfunction "A_A") (pintype "passive"))
      (node (ref "L2") (pin "A") (pinfunction "A_A") (pintype "passive"))
      (node (ref "L3V3") (pin "A") (pinfunction "A_A") (pintype "passive"))
      (node (ref "R20") (pin "2") (pinfunction "2_2") (pintype "passive"))
      (node (ref "R21") (pin "2") (pinfunction "2_2") (pintype "passive"))
      (node (ref "R22") (pin "1") (pinfunction "1_1") (pintype "passive"))
      (node (ref "R23") (pin "1") (pinfunction "1_1") (pintype "passive"))
      (node (ref "SB1") (pin "R1") (pinfunction "P$2_R1") (pintype "passive"))
      (node (ref "SB1") (pin "R2") (pinfunction "P$2_R2") (pintype "passive"))
      (node (ref "SB3") (pin "L1") (pinfunction "P$1_L1") (pintype "passive"))
      (node (ref "SB3") (pin "L2") (pinfunction "P$1_L2") (pintype "passive"))
      (node (ref "SB4") (pin "R1") (pinfunction "P$2_R1") (pintype "passive"))
      (node (ref "SB4") (pin "R2") (pinfunction "P$2_R2") (pintype "passive"))
      (node (ref "U$1") (pin "A7") (pinfunction "3.3V_A7") (pintype "bidirectional"))
      (node (ref "U$4") (pin "3") (pinfunction "IN_3") (pintype "input"))
      (node (ref "U$6") (pin "1") (pinfunction "EN_1") (pintype "bidirectional"))
      (node (ref "U$6") (pin "4") (pinfunction "VCC_4") (pintype "bidirectional"))
      (node (ref "U$7") (pin "8") (pinfunction "VCC_8") (pintype "bidirectional"))
      (node (ref "U$9") (pin "103") (pinfunction "VCCO_1_103") (pintype "bidirectional"))
      (node (ref "U$9") (pin "122") (pinfunction "VCCO_0_122") (pintype "bidirectional"))
      (node (ref "U$9") (pin "125") (pinfunction "VCCO_0_125") (pintype "bidirectional"))
      (node (ref "U$9") (pin "129") (pinfunction "VCCAUX_129") (pintype "bidirectional"))
      (node (ref "U$9") (pin "135") (pinfunction "VCCO_0_135") (pintype "bidirectional"))
      (node (ref "U$9") (pin "18") (pinfunction "VCCO_3_18") (pintype "bidirectional"))
      (node (ref "U$9") (pin "20") (pinfunction "VCCAUX_20") (pintype "bidirectional"))
      (node (ref "U$9") (pin "31") (pinfunction "VCCO_3_31") (pintype "bidirectional"))
      (node (ref "U$9") (pin "36") (pinfunction "VCCAUX_36") (pintype "bidirectional"))
      (node (ref "U$9") (pin "4") (pinfunction "VCCO_3_4") (pintype "bidirectional"))
      (node (ref "U$9") (pin "42") (pinfunction "VCCO_2_42") (pintype "bidirectional"))
      (node (ref "U$9") (pin "53") (pinfunction "VCCAUX_53") (pintype "bidirectional"))
      (node (ref "U$9") (pin "63") (pinfunction "VCCO_2_63") (pintype "bidirectional"))
      (node (ref "U$9") (pin "69") (pinfunction "P69/IO_L1N_M0_CMPMISO_2_69") (pintype "bidirectional"))
      (node (ref "U$9") (pin "76") (pinfunction "VCCO_1_76") (pintype "bidirectional"))
      (node (ref "U$9") (pin "86") (pinfunction "VCCO_1_86") (pintype "bidirectional"))
      (node (ref "U$9") (pin "90") (pinfunction "VCCAUX_90") (pintype "bidirectional"))
    )
    (net (code "96") (name "GND") (class "Default")
      (node (ref "C1") (pin "1") (pinfunction "1_1") (pintype "passive"))
      (node (ref "C10") (pin "2") (pinfunction "2_2") (pintype "passive"))
      (node (ref "C11") (pin "2") (pinfunction "2_2") (pintype "passive"))
      (node (ref "C12") (pin "2") (pinfunction "2_2") (pintype "passive"))
      (node (ref "C13") (pin "2") (pinfunction "2_2") (pintype "passive"))
      (node (ref "C14") (pin "2") (pinfunction "2_2") (pintype "passive"))
      (node (ref "C15") (pin "2") (pinfunction "2_2") (pintype "passive"))
      (node (ref "C16") (pin "2") (pinfunction "2_2") (pintype "passive"))
      (node (ref "C17") (pin "2") (pinfunction "2_2") (pintype "passive"))
      (node (ref "C18") (pin "2") (pinfunction "2_2") (pintype "passive"))
      (node (ref "C19") (pin "2") (pinfunction "2_2") (pintype "passive"))
      (node (ref "C20") (pin "2") (pinfunction "2_2") (pintype "passive"))
      (node (ref "C21") (pin "2") (pinfunction "2_2") (pintype "passive"))
      (node (ref "C22") (pin "2") (pinfunction "2_2") (pintype "passive"))
      (node (ref "C23") (pin "2") (pinfunction "2_2") (pintype "passive"))
      (node (ref "C24") (pin "2") (pinfunction "2_2") (pintype "passive"))
      (node (ref "C25") (pin "2") (pinfunction "2_2") (pintype "passive"))
      (node (ref "C26") (pin "2") (pinfunction "2_2") (pintype "passive"))
      (node (ref "C27") (pin "2") (pinfunction "2_2") (pintype "passive"))
      (node (ref "C3") (pin "2") (pinfunction "2_2") (pintype "passive"))
      (node (ref "C4") (pin "2") (pinfunction "2_2") (pintype "passive"))
      (node (ref "C5") (pin "2") (pinfunction "2_2") (pintype "passive"))
      (node (ref "C7") (pin "2") (pinfunction "2_2") (pintype "passive"))
      (node (ref "C8") (pin "2") (pinfunction "2_2") (pintype "passive"))
      (node (ref "C9") (pin "2") (pinfunction "2_2") (pintype "passive"))
      (node (ref "CLIP") (pin "P$1") (pinfunction "P_P$1") (pintype "bidirectional"))
      (node (ref "CLIP") (pin "P$2") (pinfunction "P_P$2") (pintype "bidirectional"))
      (node (ref "IC1") (pin "12") (pinfunction "VSSQ_12") (pintype "input"))
      (node (ref "IC1") (pin "28") (pinfunction "VSS_28") (pintype "input"))
      (node (ref "IC1") (pin "41") (pinfunction "VSS_41") (pintype "input"))
      (node (ref "IC1") (pin "46") (pinfunction "VSSQ_46") (pintype "input"))
      (node (ref "IC1") (pin "52") (pinfunction "VSSQ_52") (pintype "input"))
      (node (ref "IC1") (pin "54") (pinfunction "VSS_54") (pintype "input"))
      (node (ref "IC1") (pin "6") (pinfunction "VSSQ_6") (pintype "input"))
      (node (ref "JP1") (pin "1") (pinfunction "1_1") (pintype "passive"))
      (node (ref "LDONE") (pin "C") (pinfunction "C_C") (pintype "passive"))
      (node (ref "R18") (pin "1") (pinfunction "1_1") (pintype "passive"))
      (node (ref "SB2") (pin "L1") (pinfunction "P$1_L1") (pintype "passive"))
      (node (ref "U$1") (pin "A3") (pinfunction "DSEN_A3") (pintype "bidirectional"))
      (node (ref "U$1") (pin "A4") (pinfunction "GND_A4") (pintype "bidirectional"))
      (node (ref "U$1") (pin "B3") (pinfunction "MSEN_B3") (pintype "bidirectional"))
      (node (ref "U$1") (pin "B4") (pinfunction "GND_B4") (pintype "bidirectional"))
      (node (ref "U$4") (pin "1") (pinfunction "GND_1") (pintype "input"))
      (node (ref "U$6") (pin "2") (pinfunction "GND_2") (pintype "bidirectional"))
      (node (ref "U$7") (pin "4") (pinfunction "GND_4") (pintype "bidirectional"))
      (node (ref "U$9") (pin "108") (pinfunction "GND_108") (pintype "bidirectional"))
      (node (ref "U$9") (pin "113") (pinfunction "GND_113") (pintype "bidirectional"))
      (node (ref "U$9") (pin "13") (pinfunction "GND_13") (pintype "bidirectional"))
      (node (ref "U$9") (pin "130") (pinfunction "GND_130") (pintype "bidirectional"))
      (node (ref "U$9") (pin "136") (pinfunction "GND_136") (pintype "bidirectional"))
      (node (ref "U$9") (pin "25") (pinfunction "GND_25") (pintype "bidirectional"))
      (node (ref "U$9") (pin "3") (pinfunction "GND_3") (pintype "bidirectional"))
      (node (ref "U$9") (pin "49") (pinfunction "GND_49") (pintype "bidirectional"))
      (node (ref "U$9") (pin "54") (pinfunction "GND_54") (pintype "bidirectional"))
      (node (ref "U$9") (pin "60") (pinfunction "P60/IO_L13P_M1_2_60") (pintype "bidirectional"))
      (node (ref "U$9") (pin "68") (pinfunction "GND_68") (pintype "bidirectional"))
      (node (ref "U$9") (pin "73") (pinfunction "P73/SUSPEND_73") (pintype "bidirectional"))
      (node (ref "U$9") (pin "77") (pinfunction "GND_77") (pintype "bidirectional"))
      (node (ref "U$9") (pin "91") (pinfunction "GND_91") (pintype "bidirectional"))
      (node (ref "U$9") (pin "96") (pinfunction "GND_96") (pintype "bidirectional"))
      (node (ref "X2") (pin "10") (pinfunction "10_10") (pintype "passive"))
      (node (ref "X2") (pin "5") (pinfunction "5_5") (pintype "passive"))
      (node (ref "X2") (pin "6") (pinfunction "6_6") (pintype "passive"))
      (node (ref "X2") (pin "7") (pinfunction "7_7") (pintype "passive"))
      (node (ref "X2") (pin "8") (pinfunction "8_8") (pintype "passive"))
    )
    (net (code "97") (name "Net-(L0-PadC)") (class "Default")
      (node (ref "L0") (pin "C") (pinfunction "C_C") (pintype "passive"))
      (node (ref "R19") (pin "2") (pinfunction "2_2") (pintype "passive"))
    )
    (net (code "98") (name "Net-(L1-PadC)") (class "Default")
      (node (ref "L1") (pin "C") (pinfunction "C_C") (pintype "passive"))
      (node (ref "R24") (pin "2") (pinfunction "2_2") (pintype "passive"))
    )
    (net (code "99") (name "Net-(L2-PadC)") (class "Default")
      (node (ref "L2") (pin "C") (pinfunction "C_C") (pintype "passive"))
      (node (ref "R25") (pin "2") (pinfunction "2_2") (pintype "passive"))
    )
    (net (code "100") (name "Net-(L3V3-PadC)") (class "Default")
      (node (ref "L3V3") (pin "C") (pinfunction "C_C") (pintype "passive"))
      (node (ref "R18") (pin "2") (pinfunction "2_2") (pintype "passive"))
    )
    (net (code "101") (name "Net-(R1-Pad1)") (class "Default")
      (node (ref "R1") (pin "1") (pinfunction "1_1") (pintype "passive"))
      (node (ref "X2") (pin "14") (pinfunction "14_14") (pintype "passive"))
    )
    (net (code "102") (name "Net-(R2-Pad1)") (class "Default")
      (node (ref "R2") (pin "1") (pinfunction "1_1") (pintype "passive"))
      (node (ref "X2") (pin "13") (pinfunction "13_13") (pintype "passive"))
    )
    (net (code "103") (name "Net-(R10-Pad2)") (class "Default")
      (node (ref "R10") (pin "2") (pinfunction "2_2") (pintype "passive"))
      (node (ref "R13") (pin "2") (pinfunction "2_2") (pintype "passive"))
      (node (ref "R16") (pin "2") (pinfunction "2_2") (pintype "passive"))
      (node (ref "R4") (pin "2") (pinfunction "2_2") (pintype "passive"))
      (node (ref "R7") (pin "2") (pinfunction "2_2") (pintype "passive"))
      (node (ref "X2") (pin "2") (pinfunction "2_2") (pintype "passive"))
    )
    (net (code "104") (name "Net-(R11-Pad2)") (class "Default")
      (node (ref "R11") (pin "2") (pinfunction "2_2") (pintype "passive"))
      (node (ref "R14") (pin "2") (pinfunction "2_2") (pintype "passive"))
      (node (ref "R17") (pin "2") (pinfunction "2_2") (pintype "passive"))
      (node (ref "R5") (pin "2") (pinfunction "2_2") (pintype "passive"))
      (node (ref "R8") (pin "2") (pinfunction "2_2") (pintype "passive"))
      (node (ref "X2") (pin "1") (pinfunction "1_1") (pintype "passive"))
    )
    (net (code "105") (name "Net-(R12-Pad2)") (class "Default")
      (node (ref "R12") (pin "2") (pinfunction "2_2") (pintype "passive"))
      (node (ref "R15") (pin "2") (pinfunction "2_2") (pintype "passive"))
      (node (ref "R3") (pin "2") (pinfunction "2_2") (pintype "passive"))
      (node (ref "R6") (pin "2") (pinfunction "2_2") (pintype "passive"))
      (node (ref "R9") (pin "2") (pinfunction "2_2") (pintype "passive"))
      (node (ref "X2") (pin "3") (pinfunction "3_3") (pintype "passive"))
    )
    (net (code "106") (name "Net-(SB2-P$2)") (class "Default")
      (node (ref "SB1") (pin "L1") (pinfunction "P$1_L1") (pintype "passive"))
      (node (ref "SB1") (pin "L2") (pinfunction "P$1_L2") (pintype "passive"))
      (node (ref "SB2") (pin "R1") (pinfunction "P$2_R1") (pintype "passive"))
      (node (ref "U$9") (pin "144") (pinfunction "P144/IO_L1P_HSWAPEN_0_144") (pintype "bidirectional"))
    )
    (net (code "107") (name "Net-(U$9-P37{slash}PROGRAM_B_2)") (class "Default")
      (node (ref "R23") (pin "2") (pinfunction "2_2") (pintype "passive"))
      (node (ref "SB5") (pin "R1") (pinfunction "P$2_R1") (pintype "passive"))
      (node (ref "SB5") (pin "R2") (pinfunction "P$2_R2") (pintype "passive"))
      (node (ref "U$9") (pin "37") (pinfunction "P37/PROGRAM_B_2_37") (pintype "bidirectional"))
    )
    (net (code "108") (name "Net-(U$9-P39{slash}IO_L65P_INIT_B_2)") (class "Default")
      (node (ref "C1") (pin "2") (pinfunction "2_2") (pintype "passive"))
      (node (ref "INIT_B1") (pin "P") (pinfunction "P_P") (pintype "bidirectional"))
      (node (ref "R21") (pin "1") (pinfunction "1_1") (pintype "passive"))
      (node (ref "U$9") (pin "39") (pinfunction "P39/IO_L65P_INIT_B_2_39") (pintype "bidirectional"))
    )
    (net (code "109") (name "unconnected-(IC1A-NC-Pad40)") (class "Default")
      (node (ref "IC1") (pin "40") (pinfunction "NC_40") (pintype "no_connect"))
    )
    (net (code "110") (name "unconnected-(U$1-12V-PadA8)") (class "Default")
      (node (ref "U$1") (pin "A8") (pinfunction "12V_A8") (pintype "bidirectional"))
    )
    (net (code "111") (name "unconnected-(U$1-12V-PadB8)") (class "Default")
      (node (ref "U$1") (pin "B8") (pinfunction "12V_B8") (pintype "bidirectional"))
    )
    (net (code "112") (name "unconnected-(U$1-G0-PadB6)") (class "Default")
      (node (ref "U$1") (pin "B6") (pinfunction "G0_B6") (pintype "bidirectional"))
    )
    (net (code "113") (name "unconnected-(U$1-SCL-PadA5)") (class "Default")
      (node (ref "U$1") (pin "A5") (pinfunction "SCL_A5") (pintype "bidirectional"))
    )
    (net (code "114") (name "unconnected-(U$1-SDA-PadA6)") (class "Default")
      (node (ref "U$1") (pin "A6") (pinfunction "SDA_A6") (pintype "bidirectional"))
    )
    (net (code "115") (name "unconnected-(U$9-P30{slash}IO_L36P_3-Pad30)") (class "Default")
      (node (ref "U$9") (pin "30") (pinfunction "P30/IO_L36P_3_30") (pintype "bidirectional"))
    )
    (net (code "116") (name "unconnected-(U$9-P34{slash}IO_L1N_VREF_3-Pad34)") (class "Default")
      (node (ref "U$9") (pin "34") (pinfunction "P34/IO_L1N_VREF_3_34") (pintype "bidirectional"))
    )
    (net (code "117") (name "unconnected-(U$9-P35{slash}IO_L1P_3-Pad35)") (class "Default")
      (node (ref "U$9") (pin "35") (pinfunction "P35/IO_L1P_3_35") (pintype "bidirectional"))
    )
    (net (code "118") (name "unconnected-(U$9-P72{slash}CMPCS_B_2-Pad72)") (class "Default")
      (node (ref "U$9") (pin "72") (pinfunction "P72/CMPCS_B_2_72") (pintype "bidirectional"))
    )
    (net (code "119") (name "unconnected-(U$9-P82{slash}IO_L45N_1-Pad82)") (class "Default")
      (node (ref "U$9") (pin "82") (pinfunction "P82/IO_L45N_1_82") (pintype "bidirectional"))
    )
    (net (code "120") (name "unconnected-(U$9-P84{slash}IO_L43N_GCLK4_1-Pad84)") (class "Default")
      (node (ref "U$9") (pin "84") (pinfunction "P84/IO_L43N_GCLK4_1_84") (pintype "bidirectional"))
    )
    (net (code "121") (name "unconnected-(U$9-P87{slash}IO_L42N_GCLK6_TRDY1_1-Pad87)") (class "Default")
      (node (ref "U$9") (pin "87") (pinfunction "P87/IO_L42N_GCLK6_TRDY1_1_87") (pintype "bidirectional"))
    )
    (net (code "122") (name "unconnected-(U$9-P92{slash}IO_L41N_GCLK8_1-Pad92)") (class "Default")
      (node (ref "U$9") (pin "92") (pinfunction "P92/IO_L41N_GCLK8_1_92") (pintype "bidirectional"))
    )
    (net (code "123") (name "unconnected-(U$9-P111{slash}IO_L66N_SCP0_0-Pad111)") (class "Default")
      (node (ref "U$9") (pin "111") (pinfunction "P111/IO_L66N_SCP0_0_111") (pintype "bidirectional"))
    )
    (net (code "124") (name "unconnected-(U$9-P112{slash}IO_L66P_SCP1_0-Pad112)") (class "Default")
      (node (ref "U$9") (pin "112") (pinfunction "P112/IO_L66P_SCP1_0_112") (pintype "bidirectional"))
    )
    (net (code "125") (name "unconnected-(U$9-P114{slash}IO_L65N_SCP2_0-Pad114)") (class "Default")
      (node (ref "U$9") (pin "114") (pinfunction "P114/IO_L65N_SCP2_0_114") (pintype "bidirectional"))
    )
    (net (code "126") (name "unconnected-(U$9-P115{slash}IO_L65P_SCP3_0-Pad115)") (class "Default")
      (node (ref "U$9") (pin "115") (pinfunction "P115/IO_L65P_SCP3_0_115") (pintype "bidirectional"))
    )
    (net (code "127") (name "unconnected-(U$9-P116{slash}IO_L64N_SCP4_0-Pad116)") (class "Default")
      (node (ref "U$9") (pin "116") (pinfunction "P116/IO_L64N_SCP4_0_116") (pintype "bidirectional"))
    )
    (net (code "128") (name "unconnected-(X2-Pad4)") (class "Default")
      (node (ref "X2") (pin "4") (pinfunction "4_4") (pintype "passive"))
    )
    (net (code "129") (name "unconnected-(X2-Pad9)") (class "Default")
      (node (ref "X2") (pin "9") (pinfunction "9_9") (pintype "passive"))
    )
    (net (code "130") (name "unconnected-(X2-Pad11)") (class "Default")
      (node (ref "X2") (pin "11") (pinfunction "11_11") (pintype "passive"))
    )
    (net (code "131") (name "unconnected-(X2-Pad12)") (class "Default")
      (node (ref "X2") (pin "12") (pinfunction "12_12") (pintype "passive"))
    )
    (net (code "132") (name "unconnected-(X2-Pad15)") (class "Default")
      (node (ref "X2") (pin "15") (pinfunction "15_15") (pintype "passive"))
    )
  )
)
